# NixieClock.net
KiCad netlist of a schematic drawn in EAGLE
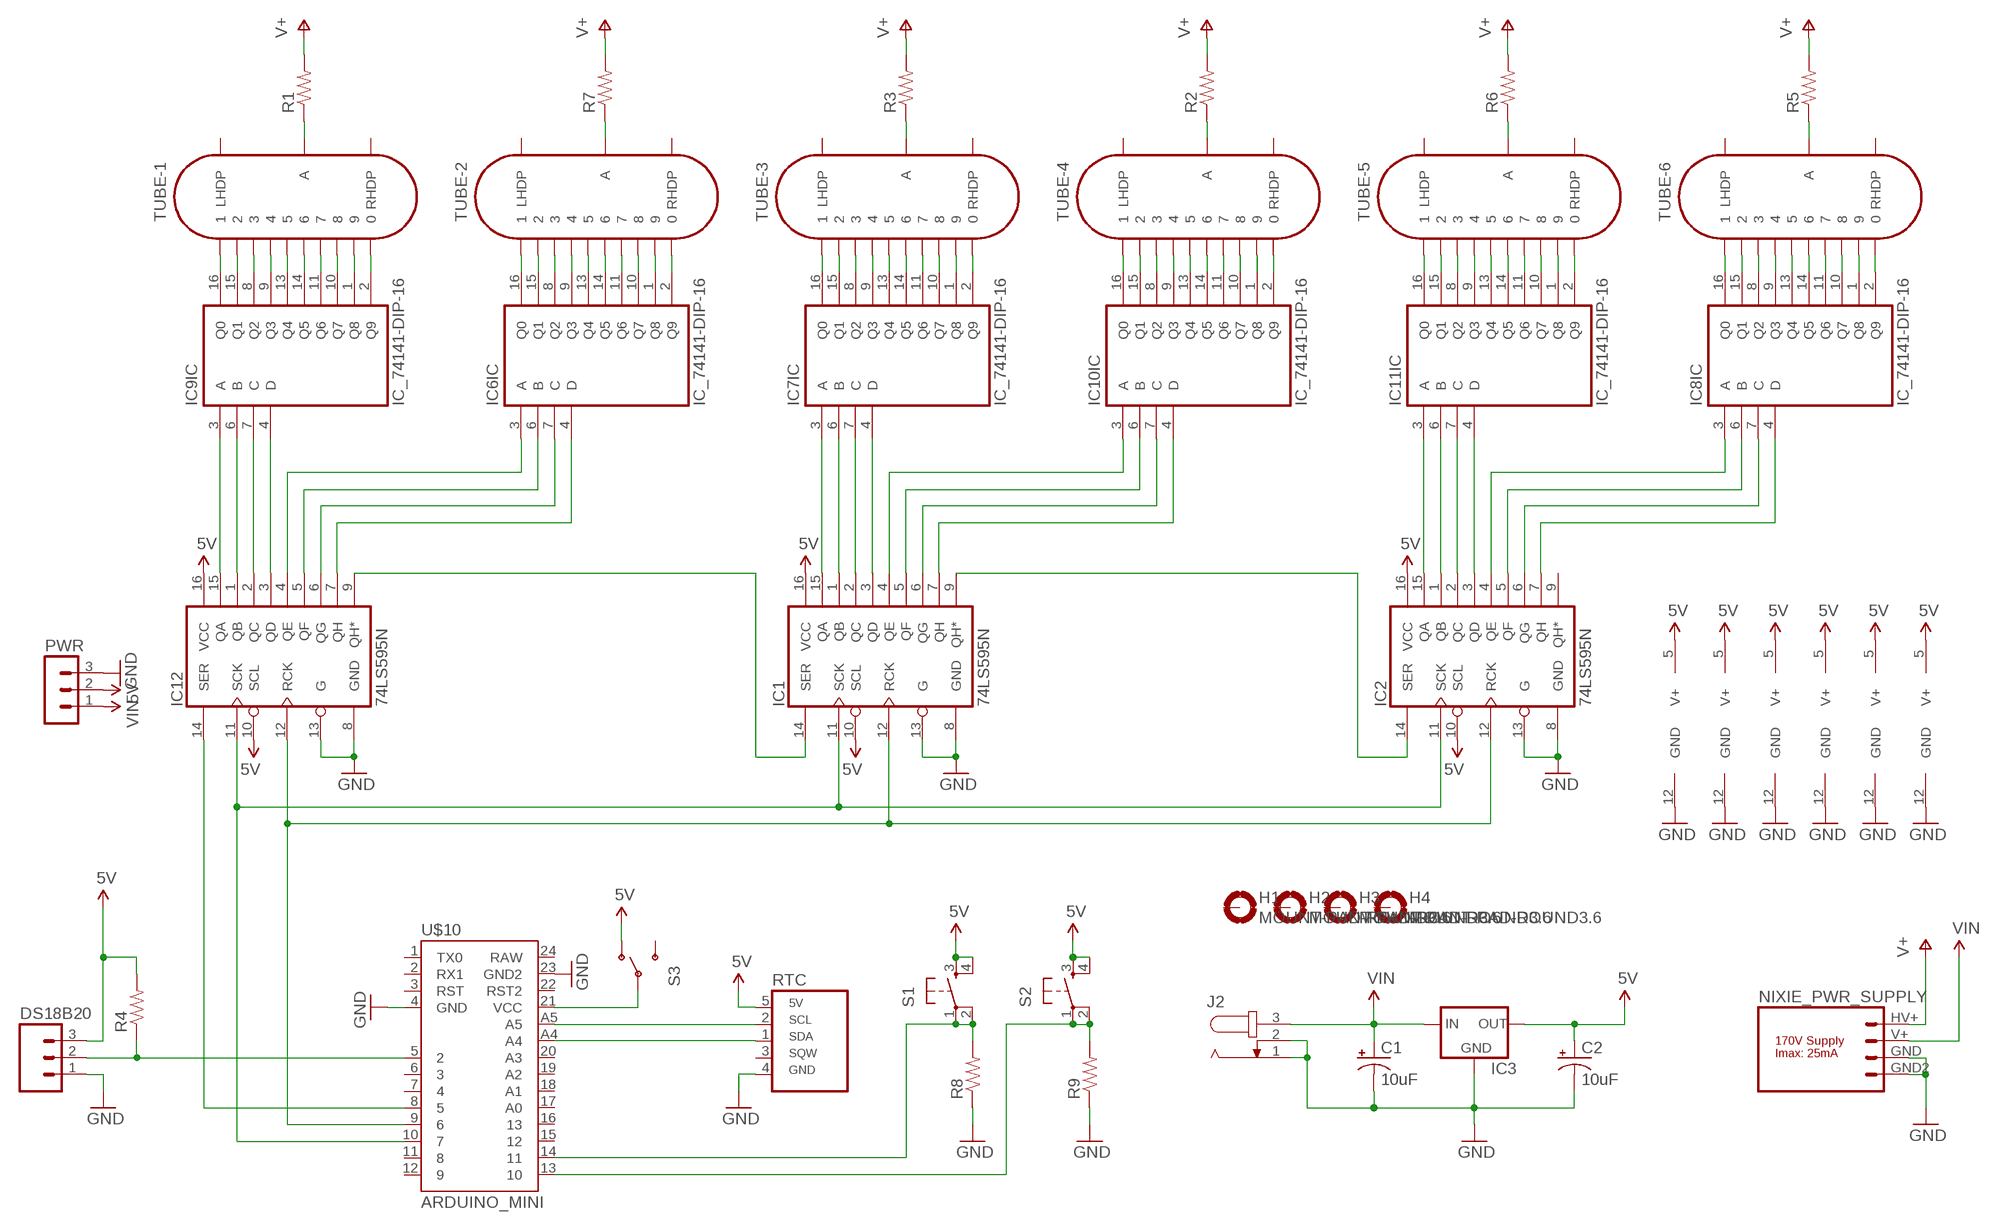
[diagram p0: schematic, sheet 1]

(export (version "E")
  (design (tool "Eeschema 10.0.6"))
  (components
    (comp (ref "C1")
      (value "10uF")
      (footprint "eagle-import:CPOL-RADIAL-10UF-25V")
      (libsource (lib "eagle-import") (part "CAP_POLPTH2"))
    )
    (comp (ref "C2")
      (value "10uF")
      (footprint "eagle-import:CPOL-RADIAL-10UF-25V")
      (libsource (lib "eagle-import") (part "CAP_POLPTH2"))
    )
    (comp (ref "DS18B20")
      (value "DS18B20DS18B20")
      (footprint "eagle-import:DS18B20")
      (libsource (lib "eagle-import") (part "DS18B20DS18B20"))
    )
    (comp (ref "H1")
      (value "MOUNT-PAD-ROUND3.6")
      (footprint "eagle-import:3,6-PAD")
      (libsource (lib "eagle-import") (part "MOUNT-PAD-ROUND3.6"))
    )
    (comp (ref "H2")
      (value "MOUNT-PAD-ROUND3.6")
      (footprint "eagle-import:3,6-PAD")
      (libsource (lib "eagle-import") (part "MOUNT-PAD-ROUND3.6"))
    )
    (comp (ref "H3")
      (value "MOUNT-PAD-ROUND3.6")
      (footprint "eagle-import:3,6-PAD")
      (libsource (lib "eagle-import") (part "MOUNT-PAD-ROUND3.6"))
    )
    (comp (ref "H4")
      (value "MOUNT-PAD-ROUND3.6")
      (footprint "eagle-import:3,6-PAD")
      (libsource (lib "eagle-import") (part "MOUNT-PAD-ROUND3.6"))
    )
    (comp (ref "IC1")
      (value "74LS595N")
      (footprint "eagle-import:DIL16")
      (libsource (lib "eagle-import") (part "74595NLS"))
    )
    (comp (ref "IC2")
      (value "74LS595N")
      (footprint "eagle-import:DIL16")
      (libsource (lib "eagle-import") (part "74595NLS"))
    )
    (comp (ref "IC3")
      (value "V_REG_78XXSIDE")
      (footprint "eagle-import:78XXL")
      (libsource (lib "eagle-import") (part "V_REG_78XXSIDE"))
    )
    (comp (ref "IC6")
      (value "IC_74141-DIP-16")
      (footprint "eagle-import:DIL16")
      (libsource (lib "eagle-import") (part "IC_74141-DIP-16"))
    )
    (comp (ref "IC7")
      (value "IC_74141-DIP-16")
      (footprint "eagle-import:DIL16")
      (libsource (lib "eagle-import") (part "IC_74141-DIP-16"))
    )
    (comp (ref "IC8")
      (value "IC_74141-DIP-16")
      (footprint "eagle-import:DIL16")
      (libsource (lib "eagle-import") (part "IC_74141-DIP-16"))
    )
    (comp (ref "IC9")
      (value "IC_74141-DIP-16")
      (footprint "eagle-import:DIL16")
      (libsource (lib "eagle-import") (part "IC_74141-DIP-16"))
    )
    (comp (ref "IC10")
      (value "IC_74141-DIP-16")
      (footprint "eagle-import:DIL16")
      (libsource (lib "eagle-import") (part "IC_74141-DIP-16"))
    )
    (comp (ref "IC11")
      (value "IC_74141-DIP-16")
      (footprint "eagle-import:DIL16")
      (libsource (lib "eagle-import") (part "IC_74141-DIP-16"))
    )
    (comp (ref "IC12")
      (value "74LS595N")
      (footprint "eagle-import:DIL16")
      (libsource (lib "eagle-import") (part "74595NLS"))
    )
    (comp (ref "J2")
      (value "JACK-PLUG0")
      (footprint "eagle-import:SPC4077")
      (libsource (lib "eagle-import") (part "JACK-PLUG0"))
    )
    (comp (ref "NIXIE_PWR_SUPPLY")
      (value "NIXIE_PWR_SUPPLYPTH")
      (footprint "eagle-import:NIXIE_PWR_SUPPLY")
      (libsource (lib "eagle-import") (part "NIXIE_PWR_SUPPLYPTH"))
    )
    (comp (ref "PWR")
      (value "MA03-1")
      (footprint "eagle-import:MA03-1")
      (libsource (lib "eagle-import") (part "MA03-1"))
    )
    (comp (ref "R1")
      (value "RESISTORPTH-1/4W")
      (footprint "eagle-import:AXIAL-0.4")
      (libsource (lib "eagle-import") (part "RESISTORPTH-1/4W"))
    )
    (comp (ref "R2")
      (value "RESISTORPTH-1/4W")
      (footprint "eagle-import:AXIAL-0.4")
      (libsource (lib "eagle-import") (part "RESISTORPTH-1/4W"))
    )
    (comp (ref "R3")
      (value "RESISTORPTH-1/4W")
      (footprint "eagle-import:AXIAL-0.4")
      (libsource (lib "eagle-import") (part "RESISTORPTH-1/4W"))
    )
    (comp (ref "R4")
      (value "RESISTORPTH-1/4W")
      (footprint "eagle-import:AXIAL-0.4")
      (libsource (lib "eagle-import") (part "SparkFun-Passives_RESISTORPTH-1/4W"))
    )
    (comp (ref "R5")
      (value "RESISTORPTH-1/4W")
      (footprint "eagle-import:AXIAL-0.4")
      (libsource (lib "eagle-import") (part "RESISTORPTH-1/4W"))
    )
    (comp (ref "R6")
      (value "RESISTORPTH-1/4W")
      (footprint "eagle-import:AXIAL-0.4")
      (libsource (lib "eagle-import") (part "RESISTORPTH-1/4W"))
    )
    (comp (ref "R7")
      (value "RESISTORPTH-1/4W")
      (footprint "eagle-import:AXIAL-0.4")
      (libsource (lib "eagle-import") (part "RESISTORPTH-1/4W"))
    )
    (comp (ref "R8")
      (value "RESISTORPTH-1/4W")
      (footprint "eagle-import:AXIAL-0.4")
      (libsource (lib "eagle-import") (part "SparkFun-Passives_RESISTORPTH-1/4W"))
    )
    (comp (ref "R9")
      (value "RESISTORPTH-1/4W")
      (footprint "eagle-import:AXIAL-0.4")
      (libsource (lib "eagle-import") (part "SparkFun-Passives_RESISTORPTH-1/4W"))
    )
    (comp (ref "RTC")
      (value "SCOTT_RTCPTH")
      (footprint "eagle-import:SCOTT_RTC")
      (libsource (lib "eagle-import") (part "SCOTT_RTCPTH"))
    )
    (comp (ref "S1")
      (value "TAC_SWITCHPTH")
      (footprint "eagle-import:TACTILE-PTH")
      (libsource (lib "eagle-import") (part "TAC_SWITCHPTH"))
    )
    (comp (ref "S2")
      (value "TAC_SWITCHPTH")
      (footprint "eagle-import:TACTILE-PTH")
      (libsource (lib "eagle-import") (part "TAC_SWITCHPTH"))
    )
    (comp (ref "S3")
      (value "SWITCH-SPDTPTH")
      (footprint "eagle-import:SWITCH-SPDT")
      (libsource (lib "eagle-import") (part "SWITCH-SPDTPTH"))
    )
    (comp (ref "TUBE-1")
      (value "IN-14")
      (footprint "eagle-import:IN-14")
      (libsource (lib "eagle-import") (part "IN-14"))
    )
    (comp (ref "TUBE-2")
      (value "IN-14")
      (footprint "eagle-import:IN-14")
      (libsource (lib "eagle-import") (part "IN-14"))
    )
    (comp (ref "TUBE-3")
      (value "IN-14")
      (footprint "eagle-import:IN-14")
      (libsource (lib "eagle-import") (part "IN-14"))
    )
    (comp (ref "TUBE-4")
      (value "IN-14")
      (footprint "eagle-import:IN-14")
      (libsource (lib "eagle-import") (part "IN-14"))
    )
    (comp (ref "TUBE-5")
      (value "IN-14")
      (footprint "eagle-import:IN-14")
      (libsource (lib "eagle-import") (part "IN-14"))
    )
    (comp (ref "TUBE-6")
      (value "IN-14")
      (footprint "eagle-import:IN-14")
      (libsource (lib "eagle-import") (part "IN-14"))
    )
    (comp (ref "U$10")
      (value "ARDUINO_MINI")
      (footprint "eagle-import:ARDUINO_MINI")
      (libsource (lib "eagle-import") (part "ARDUINO_MINI"))
    )
  )
  (nets
    (net (code "1") (name "5V") (class "Default")
      (node (ref "C2") (pin "1") (pinfunction "+_1") (pintype "passive"))
      (node (ref "DS18B20") (pin "3") (pinfunction "5V_3") (pintype "passive"))
      (node (ref "IC1") (pin "10") (pinfunction "SCL_10") (pintype "input"))
      (node (ref "IC1") (pin "16") (pinfunction "VCC_16") (pintype "power_in"))
      (node (ref "IC10") (pin "5") (pinfunction "V+_5") (pintype "power_in"))
      (node (ref "IC11") (pin "5") (pinfunction "V+_5") (pintype "power_in"))
      (node (ref "IC12") (pin "10") (pinfunction "SCL_10") (pintype "input"))
      (node (ref "IC12") (pin "16") (pinfunction "VCC_16") (pintype "power_in"))
      (node (ref "IC2") (pin "10") (pinfunction "SCL_10") (pintype "input"))
      (node (ref "IC2") (pin "16") (pinfunction "VCC_16") (pintype "power_in"))
      (node (ref "IC3") (pin "OUT") (pinfunction "OUT_OUT") (pintype "output"))
      (node (ref "IC6") (pin "5") (pinfunction "V+_5") (pintype "power_in"))
      (node (ref "IC7") (pin "5") (pinfunction "V+_5") (pintype "power_in"))
      (node (ref "IC8") (pin "5") (pinfunction "V+_5") (pintype "power_in"))
      (node (ref "IC9") (pin "5") (pinfunction "V+_5") (pintype "power_in"))
      (node (ref "PWR") (pin "2") (pinfunction "2_2") (pintype "passive"))
      (node (ref "R4") (pin "P$2") (pinfunction "2_P$2") (pintype "passive"))
      (node (ref "RTC") (pin "5") (pinfunction "5V_5") (pintype "passive"))
      (node (ref "S1") (pin "3") (pinfunction "3_3") (pintype "passive"))
      (node (ref "S1") (pin "4") (pinfunction "4_4") (pintype "passive"))
      (node (ref "S2") (pin "3") (pinfunction "3_3") (pintype "passive"))
      (node (ref "S2") (pin "4") (pinfunction "4_4") (pintype "passive"))
      (node (ref "S3") (pin "1") (pinfunction "O_1") (pintype "passive"))
    )
    (net (code "2") (name "GND") (class "Default")
      (node (ref "C1") (pin "2") (pinfunction "-_2") (pintype "passive"))
      (node (ref "C2") (pin "2") (pinfunction "-_2") (pintype "passive"))
      (node (ref "DS18B20") (pin "1") (pinfunction "GND_1") (pintype "passive"))
      (node (ref "IC1") (pin "13") (pinfunction "G_13") (pintype "input"))
      (node (ref "IC1") (pin "8") (pinfunction "GND_8") (pintype "power_in"))
      (node (ref "IC10") (pin "12") (pinfunction "GND_12") (pintype "power_in"))
      (node (ref "IC11") (pin "12") (pinfunction "GND_12") (pintype "power_in"))
      (node (ref "IC12") (pin "13") (pinfunction "G_13") (pintype "input"))
      (node (ref "IC12") (pin "8") (pinfunction "GND_8") (pintype "power_in"))
      (node (ref "IC2") (pin "13") (pinfunction "G_13") (pintype "input"))
      (node (ref "IC2") (pin "8") (pinfunction "GND_8") (pintype "power_in"))
      (node (ref "IC3") (pin "GND") (pinfunction "GND_GND") (pintype "input"))
      (node (ref "IC6") (pin "12") (pinfunction "GND_12") (pintype "power_in"))
      (node (ref "IC7") (pin "12") (pinfunction "GND_12") (pintype "power_in"))
      (node (ref "IC8") (pin "12") (pinfunction "GND_12") (pintype "power_in"))
      (node (ref "IC9") (pin "12") (pinfunction "GND_12") (pintype "power_in"))
      (node (ref "J2") (pin "1") (pinfunction "1_1") (pintype "passive"))
      (node (ref "J2") (pin "2") (pinfunction "2_2") (pintype "passive"))
      (node (ref "NIXIE_PWR_SUPPLY") (pin "GND") (pinfunction "4_GND") (pintype "passive"))
      (node (ref "NIXIE_PWR_SUPPLY") (pin "GND2") (pinfunction "1_GND2") (pintype "passive"))
      (node (ref "PWR") (pin "3") (pinfunction "3_3") (pintype "passive"))
      (node (ref "R8") (pin "P$1") (pinfunction "1_P$1") (pintype "passive"))
      (node (ref "R9") (pin "P$1") (pinfunction "1_P$1") (pintype "passive"))
      (node (ref "RTC") (pin "4") (pinfunction "GND_4") (pintype "passive"))
      (node (ref "U$10") (pin "23") (pinfunction "GND2_23") (pintype "bidirectional"))
      (node (ref "U$10") (pin "4") (pinfunction "GND_4") (pintype "bidirectional"))
    )
    (net (code "3") (name "Net-(DS18B20-DS)") (class "Default")
      (node (ref "DS18B20") (pin "2") (pinfunction "DS_2") (pintype "passive"))
      (node (ref "R4") (pin "P$1") (pinfunction "1_P$1") (pintype "passive"))
      (node (ref "U$10") (pin "5") (pinfunction "2_5") (pintype "bidirectional"))
    )
    (net (code "4") (name "Net-(IC1-QA)") (class "Default")
      (node (ref "IC1") (pin "15") (pinfunction "QA_15") (pintype "tri_state"))
      (node (ref "IC7") (pin "3") (pinfunction "A_3") (pintype "input"))
    )
    (net (code "5") (name "Net-(IC1-QB)") (class "Default")
      (node (ref "IC1") (pin "1") (pinfunction "QB_1") (pintype "tri_state"))
      (node (ref "IC7") (pin "6") (pinfunction "B_6") (pintype "input"))
    )
    (net (code "6") (name "Net-(IC1-QC)") (class "Default")
      (node (ref "IC1") (pin "2") (pinfunction "QC_2") (pintype "tri_state"))
      (node (ref "IC7") (pin "7") (pinfunction "C_7") (pintype "input"))
    )
    (net (code "7") (name "Net-(IC1-QD)") (class "Default")
      (node (ref "IC1") (pin "3") (pinfunction "QD_3") (pintype "tri_state"))
      (node (ref "IC7") (pin "4") (pinfunction "D_4") (pintype "input"))
    )
    (net (code "8") (name "Net-(IC1-QE)") (class "Default")
      (node (ref "IC1") (pin "4") (pinfunction "QE_4") (pintype "tri_state"))
      (node (ref "IC10") (pin "3") (pinfunction "A_3") (pintype "input"))
    )
    (net (code "9") (name "Net-(IC1-QF)") (class "Default")
      (node (ref "IC1") (pin "5") (pinfunction "QF_5") (pintype "tri_state"))
      (node (ref "IC10") (pin "6") (pinfunction "B_6") (pintype "input"))
    )
    (net (code "10") (name "Net-(IC1-QG)") (class "Default")
      (node (ref "IC1") (pin "6") (pinfunction "QG_6") (pintype "tri_state"))
      (node (ref "IC10") (pin "7") (pinfunction "C_7") (pintype "input"))
    )
    (net (code "11") (name "Net-(IC1-QH)") (class "Default")
      (node (ref "IC1") (pin "7") (pinfunction "QH_7") (pintype "tri_state"))
      (node (ref "IC10") (pin "4") (pinfunction "D_4") (pintype "input"))
    )
    (net (code "12") (name "Net-(IC1-QH*)") (class "Default")
      (node (ref "IC1") (pin "9") (pinfunction "QH*_9") (pintype "tri_state"))
      (node (ref "IC2") (pin "14") (pinfunction "SER_14") (pintype "input"))
    )
    (net (code "13") (name "Net-(IC1-RCK)") (class "Default")
      (node (ref "IC1") (pin "12") (pinfunction "RCK_12") (pintype "input"))
      (node (ref "IC12") (pin "12") (pinfunction "RCK_12") (pintype "input"))
      (node (ref "IC2") (pin "12") (pinfunction "RCK_12") (pintype "input"))
      (node (ref "U$10") (pin "9") (pinfunction "6_9") (pintype "bidirectional"))
    )
    (net (code "14") (name "Net-(IC1-SCK)") (class "Default")
      (node (ref "IC1") (pin "11") (pinfunction "SCK_11") (pintype "input"))
      (node (ref "IC12") (pin "11") (pinfunction "SCK_11") (pintype "input"))
      (node (ref "IC2") (pin "11") (pinfunction "SCK_11") (pintype "input"))
      (node (ref "U$10") (pin "10") (pinfunction "7_10") (pintype "bidirectional"))
    )
    (net (code "15") (name "Net-(IC1-SER)") (class "Default")
      (node (ref "IC1") (pin "14") (pinfunction "SER_14") (pintype "input"))
      (node (ref "IC12") (pin "9") (pinfunction "QH*_9") (pintype "tri_state"))
    )
    (net (code "16") (name "Net-(IC2-QE)") (class "Default")
      (node (ref "IC2") (pin "4") (pinfunction "QE_4") (pintype "tri_state"))
      (node (ref "IC8") (pin "3") (pinfunction "A_3") (pintype "input"))
    )
    (net (code "17") (name "Net-(IC2-QF)") (class "Default")
      (node (ref "IC2") (pin "5") (pinfunction "QF_5") (pintype "tri_state"))
      (node (ref "IC8") (pin "6") (pinfunction "B_6") (pintype "input"))
    )
    (net (code "18") (name "Net-(IC2-QG)") (class "Default")
      (node (ref "IC2") (pin "6") (pinfunction "QG_6") (pintype "tri_state"))
      (node (ref "IC8") (pin "7") (pinfunction "C_7") (pintype "input"))
    )
    (net (code "19") (name "Net-(IC2-QH)") (class "Default")
      (node (ref "IC2") (pin "7") (pinfunction "QH_7") (pintype "tri_state"))
      (node (ref "IC8") (pin "4") (pinfunction "D_4") (pintype "input"))
    )
    (net (code "20") (name "Net-(IC6A-Q0)") (class "Default")
      (node (ref "IC6") (pin "16") (pinfunction "Q0_16") (pintype "output"))
      (node (ref "TUBE-2") (pin "1") (pinfunction "1_1") (pintype "bidirectional"))
    )
    (net (code "21") (name "Net-(IC6A-Q1)") (class "Default")
      (node (ref "IC6") (pin "15") (pinfunction "Q1_15") (pintype "output"))
      (node (ref "TUBE-2") (pin "2") (pinfunction "2_2") (pintype "bidirectional"))
    )
    (net (code "22") (name "Net-(IC6A-Q2)") (class "Default")
      (node (ref "IC6") (pin "8") (pinfunction "Q2_8") (pintype "output"))
      (node (ref "TUBE-2") (pin "3") (pinfunction "3_3") (pintype "bidirectional"))
    )
    (net (code "23") (name "Net-(IC6A-Q3)") (class "Default")
      (node (ref "IC6") (pin "9") (pinfunction "Q3_9") (pintype "output"))
      (node (ref "TUBE-2") (pin "4") (pinfunction "4_4") (pintype "bidirectional"))
    )
    (net (code "24") (name "Net-(IC6A-Q4)") (class "Default")
      (node (ref "IC6") (pin "13") (pinfunction "Q4_13") (pintype "output"))
      (node (ref "TUBE-2") (pin "5") (pinfunction "5_5") (pintype "bidirectional"))
    )
    (net (code "25") (name "Net-(IC6A-Q5)") (class "Default")
      (node (ref "IC6") (pin "14") (pinfunction "Q5_14") (pintype "output"))
      (node (ref "TUBE-2") (pin "6") (pinfunction "6_6") (pintype "bidirectional"))
    )
    (net (code "26") (name "Net-(IC6A-Q6)") (class "Default")
      (node (ref "IC6") (pin "11") (pinfunction "Q6_11") (pintype "output"))
      (node (ref "TUBE-2") (pin "7") (pinfunction "7_7") (pintype "bidirectional"))
    )
    (net (code "27") (name "Net-(IC6A-Q7)") (class "Default")
      (node (ref "IC6") (pin "10") (pinfunction "Q7_10") (pintype "output"))
      (node (ref "TUBE-2") (pin "8") (pinfunction "8_8") (pintype "bidirectional"))
    )
    (net (code "28") (name "Net-(IC6A-Q8)") (class "Default")
      (node (ref "IC6") (pin "1") (pinfunction "Q8_1") (pintype "output"))
      (node (ref "TUBE-2") (pin "9") (pinfunction "9_9") (pintype "bidirectional"))
    )
    (net (code "29") (name "Net-(IC6A-Q9)") (class "Default")
      (node (ref "IC6") (pin "2") (pinfunction "Q9_2") (pintype "output"))
      (node (ref "TUBE-2") (pin "0") (pinfunction "0_0") (pintype "bidirectional"))
    )
    (net (code "30") (name "Net-(IC7A-Q0)") (class "Default")
      (node (ref "IC7") (pin "16") (pinfunction "Q0_16") (pintype "output"))
      (node (ref "TUBE-3") (pin "1") (pinfunction "1_1") (pintype "bidirectional"))
    )
    (net (code "31") (name "Net-(IC7A-Q1)") (class "Default")
      (node (ref "IC7") (pin "15") (pinfunction "Q1_15") (pintype "output"))
      (node (ref "TUBE-3") (pin "2") (pinfunction "2_2") (pintype "bidirectional"))
    )
    (net (code "32") (name "Net-(IC7A-Q2)") (class "Default")
      (node (ref "IC7") (pin "8") (pinfunction "Q2_8") (pintype "output"))
      (node (ref "TUBE-3") (pin "3") (pinfunction "3_3") (pintype "bidirectional"))
    )
    (net (code "33") (name "Net-(IC7A-Q3)") (class "Default")
      (node (ref "IC7") (pin "9") (pinfunction "Q3_9") (pintype "output"))
      (node (ref "TUBE-3") (pin "4") (pinfunction "4_4") (pintype "bidirectional"))
    )
    (net (code "34") (name "Net-(IC7A-Q4)") (class "Default")
      (node (ref "IC7") (pin "13") (pinfunction "Q4_13") (pintype "output"))
      (node (ref "TUBE-3") (pin "5") (pinfunction "5_5") (pintype "bidirectional"))
    )
    (net (code "35") (name "Net-(IC7A-Q5)") (class "Default")
      (node (ref "IC7") (pin "14") (pinfunction "Q5_14") (pintype "output"))
      (node (ref "TUBE-3") (pin "6") (pinfunction "6_6") (pintype "bidirectional"))
    )
    (net (code "36") (name "Net-(IC7A-Q6)") (class "Default")
      (node (ref "IC7") (pin "11") (pinfunction "Q6_11") (pintype "output"))
      (node (ref "TUBE-3") (pin "7") (pinfunction "7_7") (pintype "bidirectional"))
    )
    (net (code "37") (name "Net-(IC7A-Q7)") (class "Default")
      (node (ref "IC7") (pin "10") (pinfunction "Q7_10") (pintype "output"))
      (node (ref "TUBE-3") (pin "8") (pinfunction "8_8") (pintype "bidirectional"))
    )
    (net (code "38") (name "Net-(IC7A-Q8)") (class "Default")
      (node (ref "IC7") (pin "1") (pinfunction "Q8_1") (pintype "output"))
      (node (ref "TUBE-3") (pin "9") (pinfunction "9_9") (pintype "bidirectional"))
    )
    (net (code "39") (name "Net-(IC7A-Q9)") (class "Default")
      (node (ref "IC7") (pin "2") (pinfunction "Q9_2") (pintype "output"))
      (node (ref "TUBE-3") (pin "0") (pinfunction "0_0") (pintype "bidirectional"))
    )
    (net (code "40") (name "Net-(IC8A-Q0)") (class "Default")
      (node (ref "IC8") (pin "16") (pinfunction "Q0_16") (pintype "output"))
      (node (ref "TUBE-6") (pin "1") (pinfunction "1_1") (pintype "bidirectional"))
    )
    (net (code "41") (name "Net-(IC8A-Q1)") (class "Default")
      (node (ref "IC8") (pin "15") (pinfunction "Q1_15") (pintype "output"))
      (node (ref "TUBE-6") (pin "2") (pinfunction "2_2") (pintype "bidirectional"))
    )
    (net (code "42") (name "Net-(IC8A-Q2)") (class "Default")
      (node (ref "IC8") (pin "8") (pinfunction "Q2_8") (pintype "output"))
      (node (ref "TUBE-6") (pin "3") (pinfunction "3_3") (pintype "bidirectional"))
    )
    (net (code "43") (name "Net-(IC8A-Q3)") (class "Default")
      (node (ref "IC8") (pin "9") (pinfunction "Q3_9") (pintype "output"))
      (node (ref "TUBE-6") (pin "4") (pinfunction "4_4") (pintype "bidirectional"))
    )
    (net (code "44") (name "Net-(IC8A-Q4)") (class "Default")
      (node (ref "IC8") (pin "13") (pinfunction "Q4_13") (pintype "output"))
      (node (ref "TUBE-6") (pin "5") (pinfunction "5_5") (pintype "bidirectional"))
    )
    (net (code "45") (name "Net-(IC8A-Q5)") (class "Default")
      (node (ref "IC8") (pin "14") (pinfunction "Q5_14") (pintype "output"))
      (node (ref "TUBE-6") (pin "6") (pinfunction "6_6") (pintype "bidirectional"))
    )
    (net (code "46") (name "Net-(IC8A-Q6)") (class "Default")
      (node (ref "IC8") (pin "11") (pinfunction "Q6_11") (pintype "output"))
      (node (ref "TUBE-6") (pin "7") (pinfunction "7_7") (pintype "bidirectional"))
    )
    (net (code "47") (name "Net-(IC8A-Q7)") (class "Default")
      (node (ref "IC8") (pin "10") (pinfunction "Q7_10") (pintype "output"))
      (node (ref "TUBE-6") (pin "8") (pinfunction "8_8") (pintype "bidirectional"))
    )
    (net (code "48") (name "Net-(IC8A-Q8)") (class "Default")
      (node (ref "IC8") (pin "1") (pinfunction "Q8_1") (pintype "output"))
      (node (ref "TUBE-6") (pin "9") (pinfunction "9_9") (pintype "bidirectional"))
    )
    (net (code "49") (name "Net-(IC8A-Q9)") (class "Default")
      (node (ref "IC8") (pin "2") (pinfunction "Q9_2") (pintype "output"))
      (node (ref "TUBE-6") (pin "0") (pinfunction "0_0") (pintype "bidirectional"))
    )
    (net (code "50") (name "Net-(IC9A-Q0)") (class "Default")
      (node (ref "IC9") (pin "16") (pinfunction "Q0_16") (pintype "output"))
      (node (ref "TUBE-1") (pin "1") (pinfunction "1_1") (pintype "bidirectional"))
    )
    (net (code "51") (name "Net-(IC9A-Q1)") (class "Default")
      (node (ref "IC9") (pin "15") (pinfunction "Q1_15") (pintype "output"))
      (node (ref "TUBE-1") (pin "2") (pinfunction "2_2") (pintype "bidirectional"))
    )
    (net (code "52") (name "Net-(IC9A-Q2)") (class "Default")
      (node (ref "IC9") (pin "8") (pinfunction "Q2_8") (pintype "output"))
      (node (ref "TUBE-1") (pin "3") (pinfunction "3_3") (pintype "bidirectional"))
    )
    (net (code "53") (name "Net-(IC9A-Q3)") (class "Default")
      (node (ref "IC9") (pin "9") (pinfunction "Q3_9") (pintype "output"))
      (node (ref "TUBE-1") (pin "4") (pinfunction "4_4") (pintype "bidirectional"))
    )
    (net (code "54") (name "Net-(IC9A-Q4)") (class "Default")
      (node (ref "IC9") (pin "13") (pinfunction "Q4_13") (pintype "output"))
      (node (ref "TUBE-1") (pin "5") (pinfunction "5_5") (pintype "bidirectional"))
    )
    (net (code "55") (name "Net-(IC9A-Q5)") (class "Default")
      (node (ref "IC9") (pin "14") (pinfunction "Q5_14") (pintype "output"))
      (node (ref "TUBE-1") (pin "6") (pinfunction "6_6") (pintype "bidirectional"))
    )
    (net (code "56") (name "Net-(IC9A-Q6)") (class "Default")
      (node (ref "IC9") (pin "11") (pinfunction "Q6_11") (pintype "output"))
      (node (ref "TUBE-1") (pin "7") (pinfunction "7_7") (pintype "bidirectional"))
    )
    (net (code "57") (name "Net-(IC9A-Q7)") (class "Default")
      (node (ref "IC9") (pin "10") (pinfunction "Q7_10") (pintype "output"))
      (node (ref "TUBE-1") (pin "8") (pinfunction "8_8") (pintype "bidirectional"))
    )
    (net (code "58") (name "Net-(IC9A-Q8)") (class "Default")
      (node (ref "IC9") (pin "1") (pinfunction "Q8_1") (pintype "output"))
      (node (ref "TUBE-1") (pin "9") (pinfunction "9_9") (pintype "bidirectional"))
    )
    (net (code "59") (name "Net-(IC9A-Q9)") (class "Default")
      (node (ref "IC9") (pin "2") (pinfunction "Q9_2") (pintype "output"))
      (node (ref "TUBE-1") (pin "0") (pinfunction "0_0") (pintype "bidirectional"))
    )
    (net (code "60") (name "Net-(IC10A-Q0)") (class "Default")
      (node (ref "IC10") (pin "16") (pinfunction "Q0_16") (pintype "output"))
      (node (ref "TUBE-4") (pin "1") (pinfunction "1_1") (pintype "bidirectional"))
    )
    (net (code "61") (name "Net-(IC10A-Q1)") (class "Default")
      (node (ref "IC10") (pin "15") (pinfunction "Q1_15") (pintype "output"))
      (node (ref "TUBE-4") (pin "2") (pinfunction "2_2") (pintype "bidirectional"))
    )
    (net (code "62") (name "Net-(IC10A-Q2)") (class "Default")
      (node (ref "IC10") (pin "8") (pinfunction "Q2_8") (pintype "output"))
      (node (ref "TUBE-4") (pin "3") (pinfunction "3_3") (pintype "bidirectional"))
    )
    (net (code "63") (name "Net-(IC10A-Q3)") (class "Default")
      (node (ref "IC10") (pin "9") (pinfunction "Q3_9") (pintype "output"))
      (node (ref "TUBE-4") (pin "4") (pinfunction "4_4") (pintype "bidirectional"))
    )
    (net (code "64") (name "Net-(IC10A-Q4)") (class "Default")
      (node (ref "IC10") (pin "13") (pinfunction "Q4_13") (pintype "output"))
      (node (ref "TUBE-4") (pin "5") (pinfunction "5_5") (pintype "bidirectional"))
    )
    (net (code "65") (name "Net-(IC10A-Q5)") (class "Default")
      (node (ref "IC10") (pin "14") (pinfunction "Q5_14") (pintype "output"))
      (node (ref "TUBE-4") (pin "6") (pinfunction "6_6") (pintype "bidirectional"))
    )
    (net (code "66") (name "Net-(IC10A-Q6)") (class "Default")
      (node (ref "IC10") (pin "11") (pinfunction "Q6_11") (pintype "output"))
      (node (ref "TUBE-4") (pin "7") (pinfunction "7_7") (pintype "bidirectional"))
    )
    (net (code "67") (name "Net-(IC10A-Q7)") (class "Default")
      (node (ref "IC10") (pin "10") (pinfunction "Q7_10") (pintype "output"))
      (node (ref "TUBE-4") (pin "8") (pinfunction "8_8") (pintype "bidirectional"))
    )
    (net (code "68") (name "Net-(IC10A-Q8)") (class "Default")
      (node (ref "IC10") (pin "1") (pinfunction "Q8_1") (pintype "output"))
      (node (ref "TUBE-4") (pin "9") (pinfunction "9_9") (pintype "bidirectional"))
    )
    (net (code "69") (name "Net-(IC10A-Q9)") (class "Default")
      (node (ref "IC10") (pin "2") (pinfunction "Q9_2") (pintype "output"))
      (node (ref "TUBE-4") (pin "0") (pinfunction "0_0") (pintype "bidirectional"))
    )
    (net (code "70") (name "Net-(IC11A-A)") (class "Default")
      (node (ref "IC11") (pin "3") (pinfunction "A_3") (pintype "input"))
      (node (ref "IC2") (pin "15") (pinfunction "QA_15") (pintype "tri_state"))
    )
    (net (code "71") (name "Net-(IC11A-B)") (class "Default")
      (node (ref "IC11") (pin "6") (pinfunction "B_6") (pintype "input"))
      (node (ref "IC2") (pin "1") (pinfunction "QB_1") (pintype "tri_state"))
    )
    (net (code "72") (name "Net-(IC11A-C)") (class "Default")
      (node (ref "IC11") (pin "7") (pinfunction "C_7") (pintype "input"))
      (node (ref "IC2") (pin "2") (pinfunction "QC_2") (pintype "tri_state"))
    )
    (net (code "73") (name "Net-(IC11A-D)") (class "Default")
      (node (ref "IC11") (pin "4") (pinfunction "D_4") (pintype "input"))
      (node (ref "IC2") (pin "3") (pinfunction "QD_3") (pintype "tri_state"))
    )
    (net (code "74") (name "Net-(IC11A-Q0)") (class "Default")
      (node (ref "IC11") (pin "16") (pinfunction "Q0_16") (pintype "output"))
      (node (ref "TUBE-5") (pin "1") (pinfunction "1_1") (pintype "bidirectional"))
    )
    (net (code "75") (name "Net-(IC11A-Q1)") (class "Default")
      (node (ref "IC11") (pin "15") (pinfunction "Q1_15") (pintype "output"))
      (node (ref "TUBE-5") (pin "2") (pinfunction "2_2") (pintype "bidirectional"))
    )
    (net (code "76") (name "Net-(IC11A-Q2)") (class "Default")
      (node (ref "IC11") (pin "8") (pinfunction "Q2_8") (pintype "output"))
      (node (ref "TUBE-5") (pin "3") (pinfunction "3_3") (pintype "bidirectional"))
    )
    (net (code "77") (name "Net-(IC11A-Q3)") (class "Default")
      (node (ref "IC11") (pin "9") (pinfunction "Q3_9") (pintype "output"))
      (node (ref "TUBE-5") (pin "4") (pinfunction "4_4") (pintype "bidirectional"))
    )
    (net (code "78") (name "Net-(IC11A-Q4)") (class "Default")
      (node (ref "IC11") (pin "13") (pinfunction "Q4_13") (pintype "output"))
      (node (ref "TUBE-5") (pin "5") (pinfunction "5_5") (pintype "bidirectional"))
    )
    (net (code "79") (name "Net-(IC11A-Q5)") (class "Default")
      (node (ref "IC11") (pin "14") (pinfunction "Q5_14") (pintype "output"))
      (node (ref "TUBE-5") (pin "6") (pinfunction "6_6") (pintype "bidirectional"))
    )
    (net (code "80") (name "Net-(IC11A-Q6)") (class "Default")
      (node (ref "IC11") (pin "11") (pinfunction "Q6_11") (pintype "output"))
      (node (ref "TUBE-5") (pin "7") (pinfunction "7_7") (pintype "bidirectional"))
    )
    (net (code "81") (name "Net-(IC11A-Q7)") (class "Default")
      (node (ref "IC11") (pin "10") (pinfunction "Q7_10") (pintype "output"))
      (node (ref "TUBE-5") (pin "8") (pinfunction "8_8") (pintype "bidirectional"))
    )
    (net (code "82") (name "Net-(IC11A-Q8)") (class "Default")
      (node (ref "IC11") (pin "1") (pinfunction "Q8_1") (pintype "output"))
      (node (ref "TUBE-5") (pin "9") (pinfunction "9_9") (pintype "bidirectional"))
    )
    (net (code "83") (name "Net-(IC11A-Q9)") (class "Default")
      (node (ref "IC11") (pin "2") (pinfunction "Q9_2") (pintype "output"))
      (node (ref "TUBE-5") (pin "0") (pinfunction "0_0") (pintype "bidirectional"))
    )
    (net (code "84") (name "Net-(IC12-QA)") (class "Default")
      (node (ref "IC12") (pin "15") (pinfunction "QA_15") (pintype "tri_state"))
      (node (ref "IC9") (pin "3") (pinfunction "A_3") (pintype "input"))
    )
    (net (code "85") (name "Net-(IC12-QB)") (class "Default")
      (node (ref "IC12") (pin "1") (pinfunction "QB_1") (pintype "tri_state"))
      (node (ref "IC9") (pin "6") (pinfunction "B_6") (pintype "input"))
    )
    (net (code "86") (name "Net-(IC12-QC)") (class "Default")
      (node (ref "IC12") (pin "2") (pinfunction "QC_2") (pintype "tri_state"))
      (node (ref "IC9") (pin "7") (pinfunction "C_7") (pintype "input"))
    )
    (net (code "87") (name "Net-(IC12-QD)") (class "Default")
      (node (ref "IC12") (pin "3") (pinfunction "QD_3") (pintype "tri_state"))
      (node (ref "IC9") (pin "4") (pinfunction "D_4") (pintype "input"))
    )
    (net (code "88") (name "Net-(IC12-QE)") (class "Default")
      (node (ref "IC12") (pin "4") (pinfunction "QE_4") (pintype "tri_state"))
      (node (ref "IC6") (pin "3") (pinfunction "A_3") (pintype "input"))
    )
    (net (code "89") (name "Net-(IC12-QF)") (class "Default")
      (node (ref "IC12") (pin "5") (pinfunction "QF_5") (pintype "tri_state"))
      (node (ref "IC6") (pin "6") (pinfunction "B_6") (pintype "input"))
    )
    (net (code "90") (name "Net-(IC12-QG)") (class "Default")
      (node (ref "IC12") (pin "6") (pinfunction "QG_6") (pintype "tri_state"))
      (node (ref "IC6") (pin "7") (pinfunction "C_7") (pintype "input"))
    )
    (net (code "91") (name "Net-(IC12-QH)") (class "Default")
      (node (ref "IC12") (pin "7") (pinfunction "QH_7") (pintype "tri_state"))
      (node (ref "IC6") (pin "4") (pinfunction "D_4") (pintype "input"))
    )
    (net (code "92") (name "Net-(IC12-SER)") (class "Default")
      (node (ref "IC12") (pin "14") (pinfunction "SER_14") (pintype "input"))
      (node (ref "U$10") (pin "8") (pinfunction "5_8") (pintype "bidirectional"))
    )
    (net (code "93") (name "Net-(R1-1)") (class "Default")
      (node (ref "R1") (pin "P$1") (pinfunction "1_P$1") (pintype "passive"))
      (node (ref "TUBE-1") (pin "A") (pinfunction "A_A") (pintype "bidirectional"))
    )
    (net (code "94") (name "Net-(R2-1)") (class "Default")
      (node (ref "R2") (pin "P$1") (pinfunction "1_P$1") (pintype "passive"))
      (node (ref "TUBE-4") (pin "A") (pinfunction "A_A") (pintype "bidirectional"))
    )
    (net (code "95") (name "Net-(R3-1)") (class "Default")
      (node (ref "R3") (pin "P$1") (pinfunction "1_P$1") (pintype "passive"))
      (node (ref "TUBE-3") (pin "A") (pinfunction "A_A") (pintype "bidirectional"))
    )
    (net (code "96") (name "Net-(R5-1)") (class "Default")
      (node (ref "R5") (pin "P$1") (pinfunction "1_P$1") (pintype "passive"))
      (node (ref "TUBE-6") (pin "A") (pinfunction "A_A") (pintype "bidirectional"))
    )
    (net (code "97") (name "Net-(R6-1)") (class "Default")
      (node (ref "R6") (pin "P$1") (pinfunction "1_P$1") (pintype "passive"))
      (node (ref "TUBE-5") (pin "A") (pinfunction "A_A") (pintype "bidirectional"))
    )
    (net (code "98") (name "Net-(R7-1)") (class "Default")
      (node (ref "R7") (pin "P$1") (pinfunction "1_P$1") (pintype "passive"))
      (node (ref "TUBE-2") (pin "A") (pinfunction "A_A") (pintype "bidirectional"))
    )
    (net (code "99") (name "Net-(R8-2)") (class "Default")
      (node (ref "R8") (pin "P$2") (pinfunction "2_P$2") (pintype "passive"))
      (node (ref "S1") (pin "1") (pinfunction "1_1") (pintype "passive"))
      (node (ref "S1") (pin "2") (pinfunction "2_2") (pintype "passive"))
      (node (ref "U$10") (pin "14") (pinfunction "11_14") (pintype "bidirectional"))
    )
    (net (code "100") (name "Net-(R9-2)") (class "Default")
      (node (ref "R9") (pin "P$2") (pinfunction "2_P$2") (pintype "passive"))
      (node (ref "S2") (pin "1") (pinfunction "1_1") (pintype "passive"))
      (node (ref "S2") (pin "2") (pinfunction "2_2") (pintype "passive"))
      (node (ref "U$10") (pin "13") (pinfunction "10_13") (pintype "bidirectional"))
    )
    (net (code "101") (name "Net-(RTC-SCL)") (class "Default")
      (node (ref "RTC") (pin "2") (pinfunction "SCL_2") (pintype "passive"))
      (node (ref "U$10") (pin "A5") (pinfunction "A5_A5") (pintype "bidirectional"))
    )
    (net (code "102") (name "Net-(RTC-SDA)") (class "Default")
      (node (ref "RTC") (pin "1") (pinfunction "SDA_1") (pintype "passive"))
      (node (ref "U$10") (pin "A4") (pinfunction "A4_A4") (pintype "bidirectional"))
    )
    (net (code "103") (name "Net-(S3-P)") (class "Default")
      (node (ref "S3") (pin "2") (pinfunction "P_2") (pintype "passive"))
      (node (ref "U$10") (pin "21") (pinfunction "VCC_21") (pintype "bidirectional"))
    )
    (net (code "104") (name "V+") (class "Default")
      (node (ref "NIXIE_PWR_SUPPLY") (pin "HV+") (pinfunction "3_HV+") (pintype "passive"))
      (node (ref "R1") (pin "P$2") (pinfunction "2_P$2") (pintype "passive"))
      (node (ref "R2") (pin "P$2") (pinfunction "2_P$2") (pintype "passive"))
      (node (ref "R3") (pin "P$2") (pinfunction "2_P$2") (pintype "passive"))
      (node (ref "R5") (pin "P$2") (pinfunction "2_P$2") (pintype "passive"))
      (node (ref "R6") (pin "P$2") (pinfunction "2_P$2") (pintype "passive"))
      (node (ref "R7") (pin "P$2") (pinfunction "2_P$2") (pintype "passive"))
    )
    (net (code "105") (name "VIN") (class "Default")
      (node (ref "C1") (pin "1") (pinfunction "+_1") (pintype "passive"))
      (node (ref "IC3") (pin "IN") (pinfunction "IN_IN") (pintype "input"))
      (node (ref "J2") (pin "3") (pinfunction "3_3") (pintype "passive"))
      (node (ref "NIXIE_PWR_SUPPLY") (pin "V+") (pinfunction "2_V+") (pintype "passive"))
      (node (ref "PWR") (pin "1") (pinfunction "1_1") (pintype "passive"))
    )
    (net (code "106") (name "unconnected-(H1-MOUNT-PadB3,6)") (class "Default")
      (node (ref "H1") (pin "B3,6") (pinfunction "MOUNT_B3,6") (pintype "passive"))
    )
    (net (code "107") (name "unconnected-(H2-MOUNT-PadB3,6)") (class "Default")
      (node (ref "H2") (pin "B3,6") (pinfunction "MOUNT_B3,6") (pintype "passive"))
    )
    (net (code "108") (name "unconnected-(H3-MOUNT-PadB3,6)") (class "Default")
      (node (ref "H3") (pin "B3,6") (pinfunction "MOUNT_B3,6") (pintype "passive"))
    )
    (net (code "109") (name "unconnected-(H4-MOUNT-PadB3,6)") (class "Default")
      (node (ref "H4") (pin "B3,6") (pinfunction "MOUNT_B3,6") (pintype "passive"))
    )
    (net (code "110") (name "unconnected-(IC2-QH*-Pad9)") (class "Default")
      (node (ref "IC2") (pin "9") (pinfunction "QH*_9") (pintype "tri_state"))
    )
    (net (code "111") (name "unconnected-(RTC-SQW-Pad3)") (class "Default")
      (node (ref "RTC") (pin "3") (pinfunction "SQW_3") (pintype "passive"))
    )
    (net (code "112") (name "unconnected-(S3-S-Pad3)") (class "Default")
      (node (ref "S3") (pin "3") (pinfunction "S_3") (pintype "passive"))
    )
    (net (code "113") (name "unconnected-(TUBE-1-PadLHDP)") (class "Default")
      (node (ref "TUBE-1") (pin "LHDP") (pinfunction "LHDP_LHDP") (pintype "bidirectional"))
    )
    (net (code "114") (name "unconnected-(TUBE-1-PadRHDP)") (class "Default")
      (node (ref "TUBE-1") (pin "RHDP") (pinfunction "RHDP_RHDP") (pintype "bidirectional"))
    )
    (net (code "115") (name "unconnected-(TUBE-2-PadLHDP)") (class "Default")
      (node (ref "TUBE-2") (pin "LHDP") (pinfunction "LHDP_LHDP") (pintype "bidirectional"))
    )
    (net (code "116") (name "unconnected-(TUBE-2-PadRHDP)") (class "Default")
      (node (ref "TUBE-2") (pin "RHDP") (pinfunction "RHDP_RHDP") (pintype "bidirectional"))
    )
    (net (code "117") (name "unconnected-(TUBE-3-PadLHDP)") (class "Default")
      (node (ref "TUBE-3") (pin "LHDP") (pinfunction "LHDP_LHDP") (pintype "bidirectional"))
    )
    (net (code "118") (name "unconnected-(TUBE-3-PadRHDP)") (class "Default")
      (node (ref "TUBE-3") (pin "RHDP") (pinfunction "RHDP_RHDP") (pintype "bidirectional"))
    )
    (net (code "119") (name "unconnected-(TUBE-4-PadLHDP)") (class "Default")
      (node (ref "TUBE-4") (pin "LHDP") (pinfunction "LHDP_LHDP") (pintype "bidirectional"))
    )
    (net (code "120") (name "unconnected-(TUBE-4-PadRHDP)") (class "Default")
      (node (ref "TUBE-4") (pin "RHDP") (pinfunction "RHDP_RHDP") (pintype "bidirectional"))
    )
    (net (code "121") (name "unconnected-(TUBE-5-PadLHDP)") (class "Default")
      (node (ref "TUBE-5") (pin "LHDP") (pinfunction "LHDP_LHDP") (pintype "bidirectional"))
    )
    (net (code "122") (name "unconnected-(TUBE-5-PadRHDP)") (class "Default")
      (node (ref "TUBE-5") (pin "RHDP") (pinfunction "RHDP_RHDP") (pintype "bidirectional"))
    )
    (net (code "123") (name "unconnected-(TUBE-6-PadLHDP)") (class "Default")
      (node (ref "TUBE-6") (pin "LHDP") (pinfunction "LHDP_LHDP") (pintype "bidirectional"))
    )
    (net (code "124") (name "unconnected-(TUBE-6-PadRHDP)") (class "Default")
      (node (ref "TUBE-6") (pin "RHDP") (pinfunction "RHDP_RHDP") (pintype "bidirectional"))
    )
    (net (code "125") (name "unconnected-(U$10-3-Pad6)") (class "Default")
      (node (ref "U$10") (pin "6") (pinfunction "3_6") (pintype "bidirectional"))
    )
    (net (code "126") (name "unconnected-(U$10-4-Pad7)") (class "Default")
      (node (ref "U$10") (pin "7") (pinfunction "4_7") (pintype "bidirectional"))
    )
    (net (code "127") (name "unconnected-(U$10-8-Pad11)") (class "Default")
      (node (ref "U$10") (pin "11") (pinfunction "8_11") (pintype "bidirectional"))
    )
    (net (code "128") (name "unconnected-(U$10-9-Pad12)") (class "Default")
      (node (ref "U$10") (pin "12") (pinfunction "9_12") (pintype "bidirectional"))
    )
    (net (code "129") (name "unconnected-(U$10-12-Pad15)") (class "Default")
      (node (ref "U$10") (pin "15") (pinfunction "12_15") (pintype "bidirectional"))
    )
    (net (code "130") (name "unconnected-(U$10-13-Pad16)") (class "Default")
      (node (ref "U$10") (pin "16") (pinfunction "13_16") (pintype "bidirectional"))
    )
    (net (code "131") (name "unconnected-(U$10-A0-Pad17)") (class "Default")
      (node (ref "U$10") (pin "17") (pinfunction "A0_17") (pintype "bidirectional"))
    )
    (net (code "132") (name "unconnected-(U$10-A1-Pad18)") (class "Default")
      (node (ref "U$10") (pin "18") (pinfunction "A1_18") (pintype "bidirectional"))
    )
    (net (code "133") (name "unconnected-(U$10-A2-Pad19)") (class "Default")
      (node (ref "U$10") (pin "19") (pinfunction "A2_19") (pintype "bidirectional"))
    )
    (net (code "134") (name "unconnected-(U$10-A3-Pad20)") (class "Default")
      (node (ref "U$10") (pin "20") (pinfunction "A3_20") (pintype "bidirectional"))
    )
    (net (code "135") (name "unconnected-(U$10-RAW-Pad24)") (class "Default")
      (node (ref "U$10") (pin "24") (pinfunction "RAW_24") (pintype "bidirectional"))
    )
    (net (code "136") (name "unconnected-(U$10-RST-Pad3)") (class "Default")
      (node (ref "U$10") (pin "3") (pinfunction "RST_3") (pintype "bidirectional"))
    )
    (net (code "137") (name "unconnected-(U$10-RST2-Pad22)") (class "Default")
      (node (ref "U$10") (pin "22") (pinfunction "RST2_22") (pintype "bidirectional"))
    )
    (net (code "138") (name "unconnected-(U$10-RX1-Pad2)") (class "Default")
      (node (ref "U$10") (pin "2") (pinfunction "RX1_2") (pintype "bidirectional"))
    )
    (net (code "139") (name "unconnected-(U$10-TX0-Pad1)") (class "Default")
      (node (ref "U$10") (pin "1") (pinfunction "TX0_1") (pintype "bidirectional"))
    )
  )
)
